# lattepanda_driverstation.net
KiCad netlist of a schematic drawn in EAGLE
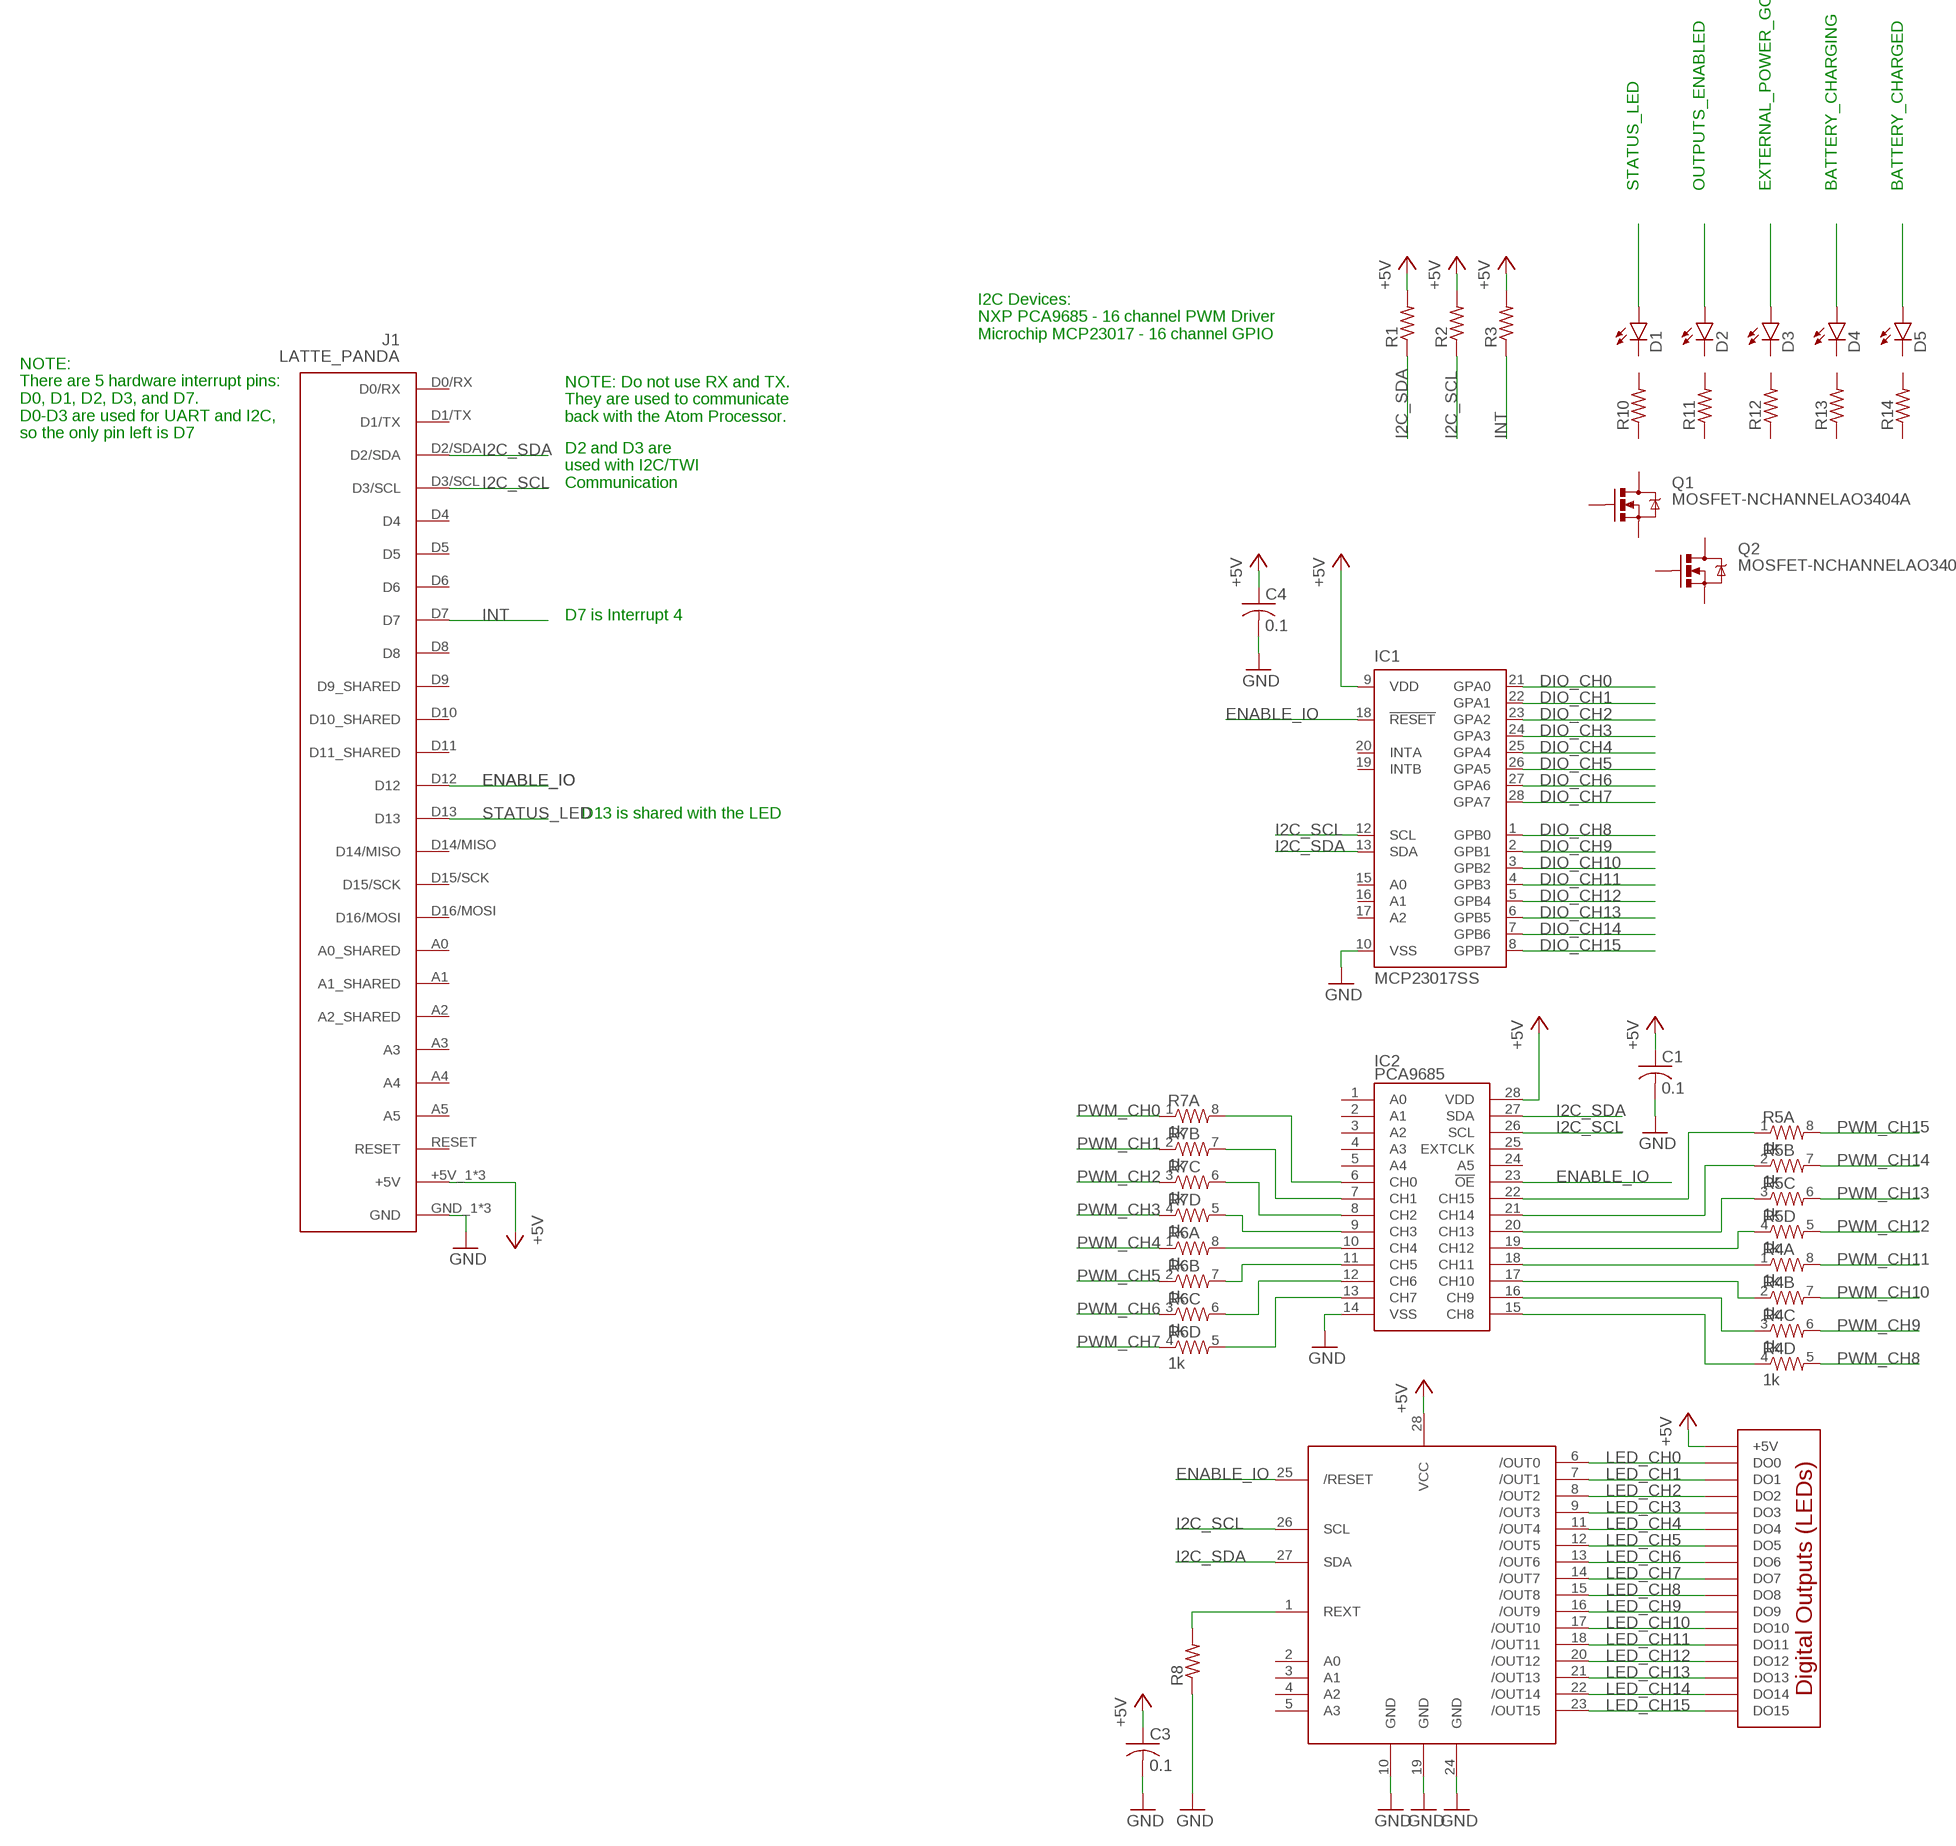
[diagram p0: schematic, sheet 1, part 1 of 2]
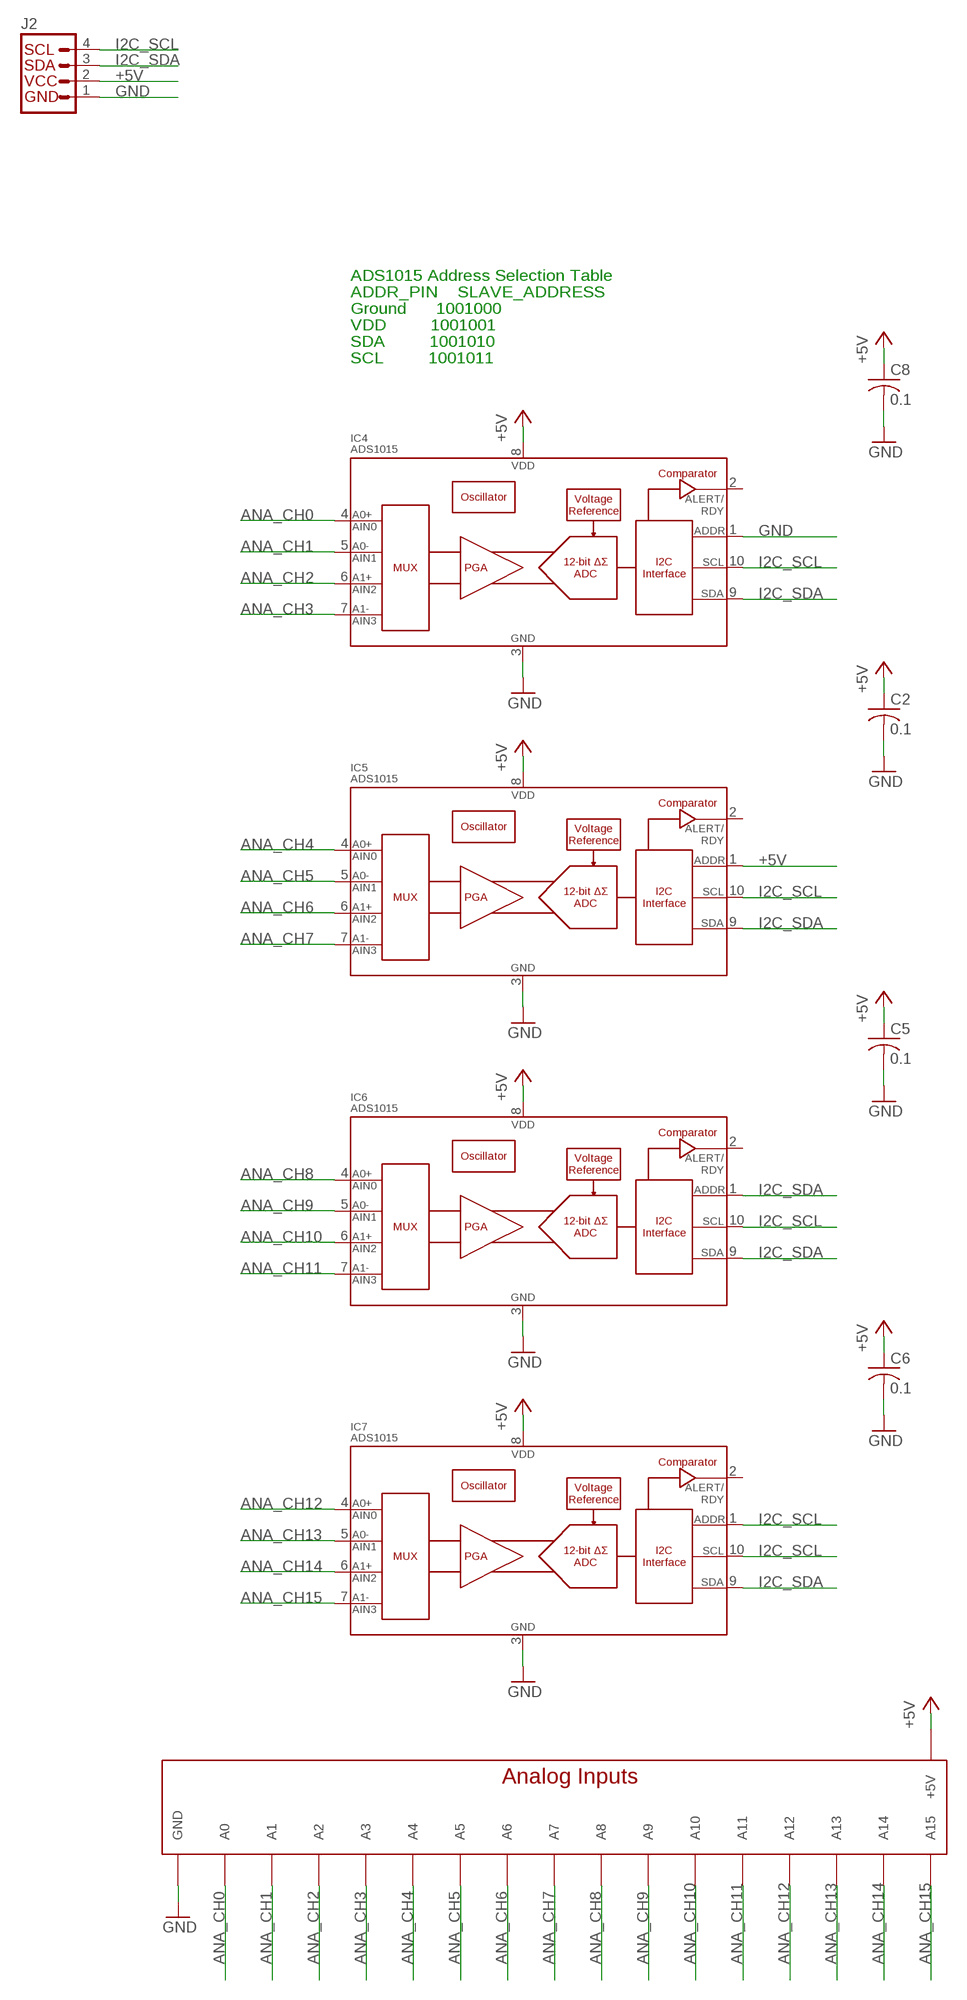
[diagram p1: schematic, sheet 1, part 2 of 2]

(export (version "E")
  (design (tool "Eeschema 10.0.6"))
  (components
    (comp (ref "C1")
      (value "0.1")
      (footprint "eagle-import:C1206")
      (libsource (lib "eagle-import") (part "C-USC1206"))
    )
    (comp (ref "C2")
      (value "0.1")
      (footprint "eagle-import:C1206")
      (libsource (lib "eagle-import") (part "C-USC1206"))
    )
    (comp (ref "C3")
      (value "0.1")
      (footprint "eagle-import:C1206")
      (libsource (lib "eagle-import") (part "C-USC1206"))
    )
    (comp (ref "C4")
      (value "0.1")
      (footprint "eagle-import:C1206")
      (libsource (lib "eagle-import") (part "C-USC1206"))
    )
    (comp (ref "C5")
      (value "0.1")
      (footprint "eagle-import:C1206")
      (libsource (lib "eagle-import") (part "C-USC1206"))
    )
    (comp (ref "C6")
      (value "0.1")
      (footprint "eagle-import:C1206")
      (libsource (lib "eagle-import") (part "C-USC1206"))
    )
    (comp (ref "C8")
      (value "0.1")
      (footprint "eagle-import:C1206")
      (libsource (lib "eagle-import") (part "C-USC1206"))
    )
    (comp (ref "D1")
      (value "LED1206")
      (footprint "eagle-import:LED-1206")
      (libsource (lib "eagle-import") (part "LED1206"))
    )
    (comp (ref "D2")
      (value "LED1206")
      (footprint "eagle-import:LED-1206")
      (libsource (lib "eagle-import") (part "LED1206"))
    )
    (comp (ref "D3")
      (value "LED1206")
      (footprint "eagle-import:LED-1206")
      (libsource (lib "eagle-import") (part "LED1206"))
    )
    (comp (ref "D4")
      (value "LED1206")
      (footprint "eagle-import:LED-1206")
      (libsource (lib "eagle-import") (part "LED1206"))
    )
    (comp (ref "D5")
      (value "LED1206")
      (footprint "eagle-import:LED-1206")
      (libsource (lib "eagle-import") (part "LED1206"))
    )
    (comp (ref "IC1")
      (value "MCP23017SS")
      (footprint "eagle-import:SSOP28")
      (fields (field (name "MF") "MICROCHIP") (field (name "MPN") "MCP23017-E/SS"))
      (libsource (lib "eagle-import") (part "MCP23017SS"))
    )
    (comp (ref "IC2")
      (value "PCA9685")
      (footprint "eagle-import:TSSOP-28_4MM")
      (libsource (lib "eagle-import") (part "PCA9685"))
    )
    (comp (ref "IC3")
      (value "TLC59116")
      (footprint "eagle-import:TSSOP28")
      (libsource (lib "eagle-import") (part "TLC59116"))
    )
    (comp (ref "IC4")
      (value "ADS1015")
      (footprint "eagle-import:MSOP10")
      (libsource (lib "eagle-import") (part "ADS1015"))
    )
    (comp (ref "IC5")
      (value "ADS1015")
      (footprint "eagle-import:MSOP10")
      (libsource (lib "eagle-import") (part "ADS1015"))
    )
    (comp (ref "IC6")
      (value "ADS1015")
      (footprint "eagle-import:MSOP10")
      (libsource (lib "eagle-import") (part "ADS1015"))
    )
    (comp (ref "IC7")
      (value "ADS1015")
      (footprint "eagle-import:MSOP10")
      (libsource (lib "eagle-import") (part "ADS1015"))
    )
    (comp (ref "J1")
      (value "LATTE_PANDA")
      (footprint "eagle-import:LATTE_PANDA")
      (libsource (lib "eagle-import") (part "LATTE_PANDA"))
    )
    (comp (ref "J2")
      (value "I2C_STANDARD")
      (footprint "eagle-import:1X04")
      (libsource (lib "eagle-import") (part "I2C_STANDARD"))
    )
    (comp (ref "Q1")
      (value "MOSFET-NCHANNELAO3404A")
      (footprint "eagle-import:SOT23-3")
      (libsource (lib "eagle-import") (part "MOSFET-NCHANNELAO3404A"))
    )
    (comp (ref "Q2")
      (value "MOSFET-NCHANNELAO3404A")
      (footprint "eagle-import:SOT23-3")
      (libsource (lib "eagle-import") (part "MOSFET-NCHANNELAO3404A"))
    )
    (comp (ref "R1")
      (value "R-US_M1206")
      (footprint "eagle-import:M1206")
      (libsource (lib "eagle-import") (part "R-US_M1206"))
    )
    (comp (ref "R2")
      (value "R-US_M1206")
      (footprint "eagle-import:M1206")
      (libsource (lib "eagle-import") (part "R-US_M1206"))
    )
    (comp (ref "R3")
      (value "R-US_M1206")
      (footprint "eagle-import:M1206")
      (libsource (lib "eagle-import") (part "R-US_M1206"))
    )
    (comp (ref "R4")
      (value "1k")
      (footprint "eagle-import:0603-ARV")
      (libsource (lib "eagle-import") (part "RESISTOR-ARRAY0603-ARV"))
    )
    (comp (ref "R5")
      (value "1k")
      (footprint "eagle-import:0603-ARV")
      (libsource (lib "eagle-import") (part "RESISTOR-ARRAY0603-ARV"))
    )
    (comp (ref "R6")
      (value "1k")
      (footprint "eagle-import:0603-ARV")
      (libsource (lib "eagle-import") (part "RESISTOR-ARRAY0603-ARV"))
    )
    (comp (ref "R7")
      (value "1k")
      (footprint "eagle-import:0603-ARV")
      (libsource (lib "eagle-import") (part "RESISTOR-ARRAY0603-ARV"))
    )
    (comp (ref "R8")
      (value "R-US_R1206")
      (footprint "eagle-import:R1206")
      (libsource (lib "eagle-import") (part "R-US_R1206"))
    )
    (comp (ref "R10")
      (value "R-US_M1206")
      (footprint "eagle-import:M1206")
      (libsource (lib "eagle-import") (part "R-US_M1206"))
    )
    (comp (ref "R11")
      (value "R-US_M1206")
      (footprint "eagle-import:M1206")
      (libsource (lib "eagle-import") (part "R-US_M1206"))
    )
    (comp (ref "R12")
      (value "R-US_M1206")
      (footprint "eagle-import:M1206")
      (libsource (lib "eagle-import") (part "R-US_M1206"))
    )
    (comp (ref "R13")
      (value "R-US_M1206")
      (footprint "eagle-import:M1206")
      (libsource (lib "eagle-import") (part "R-US_M1206"))
    )
    (comp (ref "R14")
      (value "R-US_M1206")
      (footprint "eagle-import:M1206")
      (libsource (lib "eagle-import") (part "R-US_M1206"))
    )
    (comp (ref "U$1")
      (value "ANALOGHEADER")
      (footprint "eagle-import:ANALOGHEADER")
      (libsource (lib "eagle-import") (part "ANALOGHEADER"))
    )
    (comp (ref "U$2")
      (value "DIGITALOUTPUTS")
      (footprint "eagle-import:DIGITALOUT")
      (libsource (lib "eagle-import") (part "DIGITALOUTPUTS"))
    )
  )
  (nets
    (net (code "1") (name "+5V") (class "Default")
      (node (ref "C1") (pin "1") (pinfunction "1_1") (pintype "passive"))
      (node (ref "C2") (pin "1") (pinfunction "1_1") (pintype "passive"))
      (node (ref "C3") (pin "1") (pinfunction "1_1") (pintype "passive"))
      (node (ref "C4") (pin "1") (pinfunction "1_1") (pintype "passive"))
      (node (ref "C5") (pin "1") (pinfunction "1_1") (pintype "passive"))
      (node (ref "C6") (pin "1") (pinfunction "1_1") (pintype "passive"))
      (node (ref "C8") (pin "1") (pinfunction "1_1") (pintype "passive"))
      (node (ref "IC1") (pin "9") (pinfunction "VDD_9") (pintype "power_in"))
      (node (ref "IC2") (pin "28") (pinfunction "VDD_28") (pintype "bidirectional"))
      (node (ref "IC3") (pin "28") (pinfunction "VCC_28") (pintype "bidirectional"))
      (node (ref "IC4") (pin "8") (pinfunction "VDD_8") (pintype "bidirectional"))
      (node (ref "IC5") (pin "1") (pinfunction "ADDR_1") (pintype "bidirectional"))
      (node (ref "IC5") (pin "8") (pinfunction "VDD_8") (pintype "bidirectional"))
      (node (ref "IC6") (pin "8") (pinfunction "VDD_8") (pintype "bidirectional"))
      (node (ref "IC7") (pin "8") (pinfunction "VDD_8") (pintype "bidirectional"))
      (node (ref "J1") (pin "+5V_1") (pinfunction "+5V_+5V_1") (pintype "power_in"))
      (node (ref "J1") (pin "+5V_2") (pinfunction "+5V_+5V_2") (pintype "power_in"))
      (node (ref "J1") (pin "+5V_3") (pinfunction "+5V_+5V_3") (pintype "power_in"))
      (node (ref "J2") (pin "2") (pinfunction "2_2") (pintype "passive"))
      (node (ref "R1") (pin "2") (pinfunction "2_2") (pintype "passive"))
      (node (ref "R2") (pin "2") (pinfunction "2_2") (pintype "passive"))
      (node (ref "R3") (pin "2") (pinfunction "2_2") (pintype "passive"))
      (node (ref "U$1") (pin "+5V@0") (pinfunction "+5V_+5V@0") (pintype "bidirectional"))
      (node (ref "U$1") (pin "+5V@1") (pinfunction "+5V_+5V@1") (pintype "bidirectional"))
      (node (ref "U$1") (pin "+5V@10") (pinfunction "+5V_+5V@10") (pintype "bidirectional"))
      (node (ref "U$1") (pin "+5V@11") (pinfunction "+5V_+5V@11") (pintype "bidirectional"))
      (node (ref "U$1") (pin "+5V@12") (pinfunction "+5V_+5V@12") (pintype "bidirectional"))
      (node (ref "U$1") (pin "+5V@13") (pinfunction "+5V_+5V@13") (pintype "bidirectional"))
      (node (ref "U$1") (pin "+5V@14") (pinfunction "+5V_+5V@14") (pintype "bidirectional"))
      (node (ref "U$1") (pin "+5V@15") (pinfunction "+5V_+5V@15") (pintype "bidirectional"))
      (node (ref "U$1") (pin "+5V@2") (pinfunction "+5V_+5V@2") (pintype "bidirectional"))
      (node (ref "U$1") (pin "+5V@3") (pinfunction "+5V_+5V@3") (pintype "bidirectional"))
      (node (ref "U$1") (pin "+5V@4") (pinfunction "+5V_+5V@4") (pintype "bidirectional"))
      (node (ref "U$1") (pin "+5V@5") (pinfunction "+5V_+5V@5") (pintype "bidirectional"))
      (node (ref "U$1") (pin "+5V@6") (pinfunction "+5V_+5V@6") (pintype "bidirectional"))
      (node (ref "U$1") (pin "+5V@7") (pinfunction "+5V_+5V@7") (pintype "bidirectional"))
      (node (ref "U$1") (pin "+5V@8") (pinfunction "+5V_+5V@8") (pintype "bidirectional"))
      (node (ref "U$1") (pin "+5V@9") (pinfunction "+5V_+5V@9") (pintype "bidirectional"))
      (node (ref "U$2") (pin "+5V@0") (pinfunction "+5V_+5V@0") (pintype "power_in"))
      (node (ref "U$2") (pin "+5V@1") (pinfunction "+5V_+5V@1") (pintype "power_in"))
      (node (ref "U$2") (pin "+5V@10") (pinfunction "+5V_+5V@10") (pintype "power_in"))
      (node (ref "U$2") (pin "+5V@11") (pinfunction "+5V_+5V@11") (pintype "power_in"))
      (node (ref "U$2") (pin "+5V@12") (pinfunction "+5V_+5V@12") (pintype "power_in"))
      (node (ref "U$2") (pin "+5V@13") (pinfunction "+5V_+5V@13") (pintype "power_in"))
      (node (ref "U$2") (pin "+5V@14") (pinfunction "+5V_+5V@14") (pintype "power_in"))
      (node (ref "U$2") (pin "+5V@15") (pinfunction "+5V_+5V@15") (pintype "power_in"))
      (node (ref "U$2") (pin "+5V@2") (pinfunction "+5V_+5V@2") (pintype "power_in"))
      (node (ref "U$2") (pin "+5V@3") (pinfunction "+5V_+5V@3") (pintype "power_in"))
      (node (ref "U$2") (pin "+5V@4") (pinfunction "+5V_+5V@4") (pintype "power_in"))
      (node (ref "U$2") (pin "+5V@5") (pinfunction "+5V_+5V@5") (pintype "power_in"))
      (node (ref "U$2") (pin "+5V@6") (pinfunction "+5V_+5V@6") (pintype "power_in"))
      (node (ref "U$2") (pin "+5V@7") (pinfunction "+5V_+5V@7") (pintype "power_in"))
      (node (ref "U$2") (pin "+5V@8") (pinfunction "+5V_+5V@8") (pintype "power_in"))
      (node (ref "U$2") (pin "+5V@9") (pinfunction "+5V_+5V@9") (pintype "power_in"))
    )
    (net (code "2") (name "/ANA_CH0") (class "Default")
      (node (ref "IC4") (pin "4") (pinfunction "AIN0_4") (pintype "bidirectional"))
      (node (ref "U$1") (pin "0") (pinfunction "A0_0") (pintype "bidirectional"))
    )
    (net (code "3") (name "/ANA_CH1") (class "Default")
      (node (ref "IC4") (pin "5") (pinfunction "AIN1_5") (pintype "bidirectional"))
      (node (ref "U$1") (pin "1") (pinfunction "A1_1") (pintype "bidirectional"))
    )
    (net (code "4") (name "/ANA_CH2") (class "Default")
      (node (ref "IC4") (pin "6") (pinfunction "AIN2_6") (pintype "bidirectional"))
      (node (ref "U$1") (pin "2") (pinfunction "A2_2") (pintype "bidirectional"))
    )
    (net (code "5") (name "/ANA_CH3") (class "Default")
      (node (ref "IC4") (pin "7") (pinfunction "AIN3_7") (pintype "bidirectional"))
      (node (ref "U$1") (pin "3") (pinfunction "A3_3") (pintype "bidirectional"))
    )
    (net (code "6") (name "/ANA_CH4") (class "Default")
      (node (ref "IC5") (pin "4") (pinfunction "AIN0_4") (pintype "bidirectional"))
      (node (ref "U$1") (pin "4") (pinfunction "A4_4") (pintype "bidirectional"))
    )
    (net (code "7") (name "/ANA_CH5") (class "Default")
      (node (ref "IC5") (pin "5") (pinfunction "AIN1_5") (pintype "bidirectional"))
      (node (ref "U$1") (pin "5") (pinfunction "A5_5") (pintype "bidirectional"))
    )
    (net (code "8") (name "/ANA_CH6") (class "Default")
      (node (ref "IC5") (pin "6") (pinfunction "AIN2_6") (pintype "bidirectional"))
      (node (ref "U$1") (pin "6") (pinfunction "A6_6") (pintype "bidirectional"))
    )
    (net (code "9") (name "/ANA_CH7") (class "Default")
      (node (ref "IC5") (pin "7") (pinfunction "AIN3_7") (pintype "bidirectional"))
      (node (ref "U$1") (pin "7") (pinfunction "A7_7") (pintype "bidirectional"))
    )
    (net (code "10") (name "/ANA_CH8") (class "Default")
      (node (ref "IC6") (pin "4") (pinfunction "AIN0_4") (pintype "bidirectional"))
      (node (ref "U$1") (pin "8") (pinfunction "A8_8") (pintype "bidirectional"))
    )
    (net (code "11") (name "/ANA_CH9") (class "Default")
      (node (ref "IC6") (pin "5") (pinfunction "AIN1_5") (pintype "bidirectional"))
      (node (ref "U$1") (pin "9") (pinfunction "A9_9") (pintype "bidirectional"))
    )
    (net (code "12") (name "/ANA_CH10") (class "Default")
      (node (ref "IC6") (pin "6") (pinfunction "AIN2_6") (pintype "bidirectional"))
      (node (ref "U$1") (pin "10") (pinfunction "A10_10") (pintype "bidirectional"))
    )
    (net (code "13") (name "/ANA_CH11") (class "Default")
      (node (ref "IC6") (pin "7") (pinfunction "AIN3_7") (pintype "bidirectional"))
      (node (ref "U$1") (pin "11") (pinfunction "A11_11") (pintype "bidirectional"))
    )
    (net (code "14") (name "/ANA_CH12") (class "Default")
      (node (ref "IC7") (pin "4") (pinfunction "AIN0_4") (pintype "bidirectional"))
      (node (ref "U$1") (pin "12") (pinfunction "A12_12") (pintype "bidirectional"))
    )
    (net (code "15") (name "/ANA_CH13") (class "Default")
      (node (ref "IC7") (pin "5") (pinfunction "AIN1_5") (pintype "bidirectional"))
      (node (ref "U$1") (pin "13") (pinfunction "A13_13") (pintype "bidirectional"))
    )
    (net (code "16") (name "/ANA_CH14") (class "Default")
      (node (ref "IC7") (pin "6") (pinfunction "AIN2_6") (pintype "bidirectional"))
      (node (ref "U$1") (pin "14") (pinfunction "A14_14") (pintype "bidirectional"))
    )
    (net (code "17") (name "/ANA_CH15") (class "Default")
      (node (ref "IC7") (pin "7") (pinfunction "AIN3_7") (pintype "bidirectional"))
      (node (ref "U$1") (pin "15") (pinfunction "A15_15") (pintype "bidirectional"))
    )
    (net (code "18") (name "/DIO_CH0") (class "Default")
      (node (ref "IC1") (pin "21") (pinfunction "GPA0_21") (pintype "bidirectional"))
    )
    (net (code "19") (name "/DIO_CH1") (class "Default")
      (node (ref "IC1") (pin "22") (pinfunction "GPA1_22") (pintype "bidirectional"))
    )
    (net (code "20") (name "/DIO_CH2") (class "Default")
      (node (ref "IC1") (pin "23") (pinfunction "GPA2_23") (pintype "bidirectional"))
    )
    (net (code "21") (name "/DIO_CH3") (class "Default")
      (node (ref "IC1") (pin "24") (pinfunction "GPA3_24") (pintype "bidirectional"))
    )
    (net (code "22") (name "/DIO_CH4") (class "Default")
      (node (ref "IC1") (pin "25") (pinfunction "GPA4_25") (pintype "bidirectional"))
    )
    (net (code "23") (name "/DIO_CH5") (class "Default")
      (node (ref "IC1") (pin "26") (pinfunction "GPA5_26") (pintype "bidirectional"))
    )
    (net (code "24") (name "/DIO_CH6") (class "Default")
      (node (ref "IC1") (pin "27") (pinfunction "GPA6_27") (pintype "bidirectional"))
    )
    (net (code "25") (name "/DIO_CH7") (class "Default")
      (node (ref "IC1") (pin "28") (pinfunction "GPA7_28") (pintype "bidirectional"))
    )
    (net (code "26") (name "/DIO_CH8") (class "Default")
      (node (ref "IC1") (pin "1") (pinfunction "GPB0_1") (pintype "bidirectional"))
    )
    (net (code "27") (name "/DIO_CH9") (class "Default")
      (node (ref "IC1") (pin "2") (pinfunction "GPB1_2") (pintype "bidirectional"))
    )
    (net (code "28") (name "/DIO_CH10") (class "Default")
      (node (ref "IC1") (pin "3") (pinfunction "GPB2_3") (pintype "bidirectional"))
    )
    (net (code "29") (name "/DIO_CH11") (class "Default")
      (node (ref "IC1") (pin "4") (pinfunction "GPB3_4") (pintype "bidirectional"))
    )
    (net (code "30") (name "/DIO_CH12") (class "Default")
      (node (ref "IC1") (pin "5") (pinfunction "GPB4_5") (pintype "bidirectional"))
    )
    (net (code "31") (name "/DIO_CH13") (class "Default")
      (node (ref "IC1") (pin "6") (pinfunction "GPB5_6") (pintype "bidirectional"))
    )
    (net (code "32") (name "/DIO_CH14") (class "Default")
      (node (ref "IC1") (pin "7") (pinfunction "GPB6_7") (pintype "bidirectional"))
    )
    (net (code "33") (name "/DIO_CH15") (class "Default")
      (node (ref "IC1") (pin "8") (pinfunction "GPB7_8") (pintype "bidirectional"))
    )
    (net (code "34") (name "/ENABLE_IO") (class "Default")
      (node (ref "IC1") (pin "18") (pinfunction "~{RESET}_18") (pintype "input"))
      (node (ref "IC2") (pin "23") (pinfunction "~{OE}_23") (pintype "bidirectional"))
      (node (ref "IC3") (pin "25") (pinfunction "/RESET_25") (pintype "bidirectional"))
      (node (ref "J1") (pin "D12") (pinfunction "D12_D12") (pintype "bidirectional"))
    )
    (net (code "35") (name "/I2C_SCL") (class "Default")
      (node (ref "IC1") (pin "12") (pinfunction "SCL_12") (pintype "input"))
      (node (ref "IC2") (pin "26") (pinfunction "SCL_26") (pintype "bidirectional"))
      (node (ref "IC3") (pin "26") (pinfunction "SCL_26") (pintype "bidirectional"))
      (node (ref "IC4") (pin "10") (pinfunction "SCL_10") (pintype "bidirectional"))
      (node (ref "IC5") (pin "10") (pinfunction "SCL_10") (pintype "bidirectional"))
      (node (ref "IC6") (pin "10") (pinfunction "SCL_10") (pintype "bidirectional"))
      (node (ref "IC7") (pin "1") (pinfunction "ADDR_1") (pintype "bidirectional"))
      (node (ref "IC7") (pin "10") (pinfunction "SCL_10") (pintype "bidirectional"))
      (node (ref "J1") (pin "D3/SCL") (pinfunction "D3/SCL_D3/SCL") (pintype "bidirectional"))
      (node (ref "J2") (pin "4") (pinfunction "4_4") (pintype "passive"))
      (node (ref "R2") (pin "1") (pinfunction "1_1") (pintype "passive"))
    )
    (net (code "36") (name "/I2C_SDA") (class "Default")
      (node (ref "IC1") (pin "13") (pinfunction "SDA_13") (pintype "bidirectional"))
      (node (ref "IC2") (pin "27") (pinfunction "SDA_27") (pintype "bidirectional"))
      (node (ref "IC3") (pin "27") (pinfunction "SDA_27") (pintype "bidirectional"))
      (node (ref "IC4") (pin "9") (pinfunction "SDA_9") (pintype "bidirectional"))
      (node (ref "IC5") (pin "9") (pinfunction "SDA_9") (pintype "bidirectional"))
      (node (ref "IC6") (pin "1") (pinfunction "ADDR_1") (pintype "bidirectional"))
      (node (ref "IC6") (pin "9") (pinfunction "SDA_9") (pintype "bidirectional"))
      (node (ref "IC7") (pin "9") (pinfunction "SDA_9") (pintype "bidirectional"))
      (node (ref "J1") (pin "D2/SDA") (pinfunction "D2/SDA_D2/SDA") (pintype "bidirectional"))
      (node (ref "J2") (pin "3") (pinfunction "3_3") (pintype "passive"))
      (node (ref "R1") (pin "1") (pinfunction "1_1") (pintype "passive"))
    )
    (net (code "37") (name "/INT") (class "Default")
      (node (ref "J1") (pin "D7") (pinfunction "D7_D7") (pintype "bidirectional"))
      (node (ref "R3") (pin "1") (pinfunction "1_1") (pintype "passive"))
    )
    (net (code "38") (name "/LED_CH0") (class "Default")
      (node (ref "IC3") (pin "6") (pinfunction "/OUT0_6") (pintype "bidirectional"))
      (node (ref "U$2") (pin "DO0") (pinfunction "DO0_DO0") (pintype "bidirectional"))
    )
    (net (code "39") (name "/LED_CH1") (class "Default")
      (node (ref "IC3") (pin "7") (pinfunction "/OUT1_7") (pintype "bidirectional"))
      (node (ref "U$2") (pin "DO1") (pinfunction "DO1_DO1") (pintype "bidirectional"))
    )
    (net (code "40") (name "/LED_CH2") (class "Default")
      (node (ref "IC3") (pin "8") (pinfunction "/OUT2_8") (pintype "bidirectional"))
      (node (ref "U$2") (pin "DO2") (pinfunction "DO2_DO2") (pintype "bidirectional"))
    )
    (net (code "41") (name "/LED_CH3") (class "Default")
      (node (ref "IC3") (pin "9") (pinfunction "/OUT3_9") (pintype "bidirectional"))
      (node (ref "U$2") (pin "DO3") (pinfunction "DO3_DO3") (pintype "bidirectional"))
    )
    (net (code "42") (name "/LED_CH4") (class "Default")
      (node (ref "IC3") (pin "11") (pinfunction "/OUT4_11") (pintype "bidirectional"))
      (node (ref "U$2") (pin "DO4") (pinfunction "DO4_DO4") (pintype "bidirectional"))
    )
    (net (code "43") (name "/LED_CH5") (class "Default")
      (node (ref "IC3") (pin "12") (pinfunction "/OUT5_12") (pintype "bidirectional"))
      (node (ref "U$2") (pin "DO5") (pinfunction "DO5_DO5") (pintype "bidirectional"))
    )
    (net (code "44") (name "/LED_CH6") (class "Default")
      (node (ref "IC3") (pin "13") (pinfunction "/OUT6_13") (pintype "bidirectional"))
      (node (ref "U$2") (pin "DO6") (pinfunction "DO6_DO6") (pintype "bidirectional"))
    )
    (net (code "45") (name "/LED_CH7") (class "Default")
      (node (ref "IC3") (pin "14") (pinfunction "/OUT7_14") (pintype "bidirectional"))
      (node (ref "U$2") (pin "DO7") (pinfunction "DO7_DO7") (pintype "bidirectional"))
    )
    (net (code "46") (name "/LED_CH8") (class "Default")
      (node (ref "IC3") (pin "15") (pinfunction "/OUT8_15") (pintype "bidirectional"))
      (node (ref "U$2") (pin "DO8") (pinfunction "DO8_DO8") (pintype "bidirectional"))
    )
    (net (code "47") (name "/LED_CH9") (class "Default")
      (node (ref "IC3") (pin "16") (pinfunction "/OUT9_16") (pintype "bidirectional"))
      (node (ref "U$2") (pin "DO9") (pinfunction "DO9_DO9") (pintype "bidirectional"))
    )
    (net (code "48") (name "/LED_CH10") (class "Default")
      (node (ref "IC3") (pin "17") (pinfunction "/OUT10_17") (pintype "bidirectional"))
      (node (ref "U$2") (pin "DO10") (pinfunction "DO10_DO10") (pintype "bidirectional"))
    )
    (net (code "49") (name "/LED_CH11") (class "Default")
      (node (ref "IC3") (pin "18") (pinfunction "/OUT11_18") (pintype "bidirectional"))
      (node (ref "U$2") (pin "DO11") (pinfunction "DO11_DO11") (pintype "bidirectional"))
    )
    (net (code "50") (name "/LED_CH12") (class "Default")
      (node (ref "IC3") (pin "20") (pinfunction "/OUT12_20") (pintype "bidirectional"))
      (node (ref "U$2") (pin "DO12") (pinfunction "DO12_DO12") (pintype "bidirectional"))
    )
    (net (code "51") (name "/LED_CH13") (class "Default")
      (node (ref "IC3") (pin "21") (pinfunction "/OUT13_21") (pintype "bidirectional"))
      (node (ref "U$2") (pin "DO13") (pinfunction "DO13_DO13") (pintype "bidirectional"))
    )
    (net (code "52") (name "/LED_CH14") (class "Default")
      (node (ref "IC3") (pin "22") (pinfunction "/OUT14_22") (pintype "bidirectional"))
      (node (ref "U$2") (pin "DO14") (pinfunction "DO14_DO14") (pintype "bidirectional"))
    )
    (net (code "53") (name "/LED_CH15") (class "Default")
      (node (ref "IC3") (pin "23") (pinfunction "/OUT15_23") (pintype "bidirectional"))
      (node (ref "U$2") (pin "DO15") (pinfunction "DO15_DO15") (pintype "bidirectional"))
    )
    (net (code "54") (name "/PWM_CH0") (class "Default")
      (node (ref "R7") (pin "1") (pinfunction "1_1") (pintype "passive"))
    )
    (net (code "55") (name "/PWM_CH1") (class "Default")
      (node (ref "R7") (pin "2") (pinfunction "1_2") (pintype "passive"))
    )
    (net (code "56") (name "/PWM_CH2") (class "Default")
      (node (ref "R7") (pin "3") (pinfunction "1_3") (pintype "passive"))
    )
    (net (code "57") (name "/PWM_CH3") (class "Default")
      (node (ref "R7") (pin "4") (pinfunction "1_4") (pintype "passive"))
    )
    (net (code "58") (name "/PWM_CH4") (class "Default")
      (node (ref "R6") (pin "1") (pinfunction "1_1") (pintype "passive"))
    )
    (net (code "59") (name "/PWM_CH5") (class "Default")
      (node (ref "R6") (pin "2") (pinfunction "1_2") (pintype "passive"))
    )
    (net (code "60") (name "/PWM_CH6") (class "Default")
      (node (ref "R6") (pin "3") (pinfunction "1_3") (pintype "passive"))
    )
    (net (code "61") (name "/PWM_CH7") (class "Default")
      (node (ref "R6") (pin "4") (pinfunction "1_4") (pintype "passive"))
    )
    (net (code "62") (name "/PWM_CH8") (class "Default")
      (node (ref "R4") (pin "5") (pinfunction "2_5") (pintype "passive"))
    )
    (net (code "63") (name "/PWM_CH9") (class "Default")
      (node (ref "R4") (pin "6") (pinfunction "2_6") (pintype "passive"))
    )
    (net (code "64") (name "/PWM_CH10") (class "Default")
      (node (ref "R4") (pin "7") (pinfunction "2_7") (pintype "passive"))
    )
    (net (code "65") (name "/PWM_CH11") (class "Default")
      (node (ref "R4") (pin "8") (pinfunction "2_8") (pintype "passive"))
    )
    (net (code "66") (name "/PWM_CH12") (class "Default")
      (node (ref "R5") (pin "5") (pinfunction "2_5") (pintype "passive"))
    )
    (net (code "67") (name "/PWM_CH13") (class "Default")
      (node (ref "R5") (pin "6") (pinfunction "2_6") (pintype "passive"))
    )
    (net (code "68") (name "/PWM_CH14") (class "Default")
      (node (ref "R5") (pin "7") (pinfunction "2_7") (pintype "passive"))
    )
    (net (code "69") (name "/PWM_CH15") (class "Default")
      (node (ref "R5") (pin "8") (pinfunction "2_8") (pintype "passive"))
    )
    (net (code "70") (name "/STATUS_LED") (class "Default")
      (node (ref "J1") (pin "D13") (pinfunction "D13_D13") (pintype "bidirectional"))
    )
    (net (code "71") (name "GND") (class "Default")
      (node (ref "C1") (pin "2") (pinfunction "2_2") (pintype "passive"))
      (node (ref "C2") (pin "2") (pinfunction "2_2") (pintype "passive"))
      (node (ref "C3") (pin "2") (pinfunction "2_2") (pintype "passive"))
      (node (ref "C4") (pin "2") (pinfunction "2_2") (pintype "passive"))
      (node (ref "C5") (pin "2") (pinfunction "2_2") (pintype "passive"))
      (node (ref "C6") (pin "2") (pinfunction "2_2") (pintype "passive"))
      (node (ref "C8") (pin "2") (pinfunction "2_2") (pintype "passive"))
      (node (ref "IC1") (pin "10") (pinfunction "VSS_10") (pintype "power_in"))
      (node (ref "IC2") (pin "14") (pinfunction "VSS_14") (pintype "bidirectional"))
      (node (ref "IC3") (pin "10") (pinfunction "GND_10") (pintype "bidirectional"))
      (node (ref "IC3") (pin "19") (pinfunction "GND_19") (pintype "bidirectional"))
      (node (ref "IC3") (pin "24") (pinfunction "GND_24") (pintype "bidirectional"))
      (node (ref "IC4") (pin "1") (pinfunction "ADDR_1") (pintype "bidirectional"))
      (node (ref "IC4") (pin "3") (pinfunction "VSS_3") (pintype "bidirectional"))
      (node (ref "IC5") (pin "3") (pinfunction "VSS_3") (pintype "bidirectional"))
      (node (ref "IC6") (pin "3") (pinfunction "VSS_3") (pintype "bidirectional"))
      (node (ref "IC7") (pin "3") (pinfunction "VSS_3") (pintype "bidirectional"))
      (node (ref "J1") (pin "GND_1") (pinfunction "GND_GND_1") (pintype "power_in"))
      (node (ref "J1") (pin "GND_2") (pinfunction "GND_GND_2") (pintype "power_in"))
      (node (ref "J1") (pin "GND_3") (pinfunction "GND_GND_3") (pintype "power_in"))
      (node (ref "J2") (pin "1") (pinfunction "1_1") (pintype "passive"))
      (node (ref "R8") (pin "1") (pinfunction "1_1") (pintype "passive"))
      (node (ref "U$1") (pin "GND@0") (pinfunction "GND_GND@0") (pintype "bidirectional"))
      (node (ref "U$1") (pin "GND@1") (pinfunction "GND_GND@1") (pintype "bidirectional"))
      (node (ref "U$1") (pin "GND@10") (pinfunction "GND_GND@10") (pintype "bidirectional"))
      (node (ref "U$1") (pin "GND@11") (pinfunction "GND_GND@11") (pintype "bidirectional"))
      (node (ref "U$1") (pin "GND@12") (pinfunction "GND_GND@12") (pintype "bidirectional"))
      (node (ref "U$1") (pin "GND@13") (pinfunction "GND_GND@13") (pintype "bidirectional"))
      (node (ref "U$1") (pin "GND@14") (pinfunction "GND_GND@14") (pintype "bidirectional"))
      (node (ref "U$1") (pin "GND@15") (pinfunction "GND_GND@15") (pintype "bidirectional"))
      (node (ref "U$1") (pin "GND@2") (pinfunction "GND_GND@2") (pintype "bidirectional"))
      (node (ref "U$1") (pin "GND@3") (pinfunction "GND_GND@3") (pintype "bidirectional"))
      (node (ref "U$1") (pin "GND@4") (pinfunction "GND_GND@4") (pintype "bidirectional"))
      (node (ref "U$1") (pin "GND@5") (pinfunction "GND_GND@5") (pintype "bidirectional"))
      (node (ref "U$1") (pin "GND@6") (pinfunction "GND_GND@6") (pintype "bidirectional"))
      (node (ref "U$1") (pin "GND@7") (pinfunction "GND_GND@7") (pintype "bidirectional"))
      (node (ref "U$1") (pin "GND@8") (pinfunction "GND_GND@8") (pintype "bidirectional"))
      (node (ref "U$1") (pin "GND@9") (pinfunction "GND_GND@9") (pintype "bidirectional"))
    )
    (net (code "72") (name "Net-(IC2-CH0)") (class "Default")
      (node (ref "IC2") (pin "6") (pinfunction "CH0_6") (pintype "bidirectional"))
      (node (ref "R7") (pin "8") (pinfunction "2_8") (pintype "passive"))
    )
    (net (code "73") (name "Net-(IC2-CH1)") (class "Default")
      (node (ref "IC2") (pin "7") (pinfunction "CH1_7") (pintype "bidirectional"))
      (node (ref "R7") (pin "7") (pinfunction "2_7") (pintype "passive"))
    )
    (net (code "74") (name "Net-(IC2-CH2)") (class "Default")
      (node (ref "IC2") (pin "8") (pinfunction "CH2_8") (pintype "bidirectional"))
      (node (ref "R7") (pin "6") (pinfunction "2_6") (pintype "passive"))
    )
    (net (code "75") (name "Net-(IC2-CH3)") (class "Default")
      (node (ref "IC2") (pin "9") (pinfunction "CH3_9") (pintype "bidirectional"))
      (node (ref "R7") (pin "5") (pinfunction "2_5") (pintype "passive"))
    )
    (net (code "76") (name "Net-(IC2-CH4)") (class "Default")
      (node (ref "IC2") (pin "10") (pinfunction "CH4_10") (pintype "bidirectional"))
      (node (ref "R6") (pin "8") (pinfunction "2_8") (pintype "passive"))
    )
    (net (code "77") (name "Net-(IC2-CH5)") (class "Default")
      (node (ref "IC2") (pin "11") (pinfunction "CH5_11") (pintype "bidirectional"))
      (node (ref "R6") (pin "7") (pinfunction "2_7") (pintype "passive"))
    )
    (net (code "78") (name "Net-(IC2-CH6)") (class "Default")
      (node (ref "IC2") (pin "12") (pinfunction "CH6_12") (pintype "bidirectional"))
      (node (ref "R6") (pin "6") (pinfunction "2_6") (pintype "passive"))
    )
    (net (code "79") (name "Net-(IC2-CH7)") (class "Default")
      (node (ref "IC2") (pin "13") (pinfunction "CH7_13") (pintype "bidirectional"))
      (node (ref "R6") (pin "5") (pinfunction "2_5") (pintype "passive"))
    )
    (net (code "80") (name "Net-(IC2-CH8)") (class "Default")
      (node (ref "IC2") (pin "15") (pinfunction "CH8_15") (pintype "bidirectional"))
      (node (ref "R4") (pin "4") (pinfunction "1_4") (pintype "passive"))
    )
    (net (code "81") (name "Net-(IC2-CH9)") (class "Default")
      (node (ref "IC2") (pin "16") (pinfunction "CH9_16") (pintype "bidirectional"))
      (node (ref "R4") (pin "3") (pinfunction "1_3") (pintype "passive"))
    )
    (net (code "82") (name "Net-(IC2-CH10)") (class "Default")
      (node (ref "IC2") (pin "17") (pinfunction "CH10_17") (pintype "bidirectional"))
      (node (ref "R4") (pin "2") (pinfunction "1_2") (pintype "passive"))
    )
    (net (code "83") (name "Net-(IC2-CH11)") (class "Default")
      (node (ref "IC2") (pin "18") (pinfunction "CH11_18") (pintype "bidirectional"))
      (node (ref "R4") (pin "1") (pinfunction "1_1") (pintype "passive"))
    )
    (net (code "84") (name "Net-(IC2-CH12)") (class "Default")
      (node (ref "IC2") (pin "19") (pinfunction "CH12_19") (pintype "bidirectional"))
      (node (ref "R5") (pin "4") (pinfunction "1_4") (pintype "passive"))
    )
    (net (code "85") (name "Net-(IC2-CH13)") (class "Default")
      (node (ref "IC2") (pin "20") (pinfunction "CH13_20") (pintype "bidirectional"))
      (node (ref "R5") (pin "3") (pinfunction "1_3") (pintype "passive"))
    )
    (net (code "86") (name "Net-(IC2-CH14)") (class "Default")
      (node (ref "IC2") (pin "21") (pinfunction "CH14_21") (pintype "bidirectional"))
      (node (ref "R5") (pin "2") (pinfunction "1_2") (pintype "passive"))
    )
    (net (code "87") (name "Net-(IC2-CH15)") (class "Default")
      (node (ref "IC2") (pin "22") (pinfunction "CH15_22") (pintype "bidirectional"))
      (node (ref "R5") (pin "1") (pinfunction "1_1") (pintype "passive"))
    )
    (net (code "88") (name "Net-(IC3-REXT)") (class "Default")
      (node (ref "IC3") (pin "1") (pinfunction "REXT_1") (pintype "bidirectional"))
      (node (ref "R8") (pin "2") (pinfunction "2_2") (pintype "passive"))
    )
    (net (code "89") (name "unconnected-(D1-PadA)") (class "Default")
      (node (ref "D1") (pin "A") (pinfunction "A_A") (pintype "passive"))
    )
    (net (code "90") (name "unconnected-(D1-PadC)") (class "Default")
      (node (ref "D1") (pin "C") (pinfunction "C_C") (pintype "passive"))
    )
    (net (code "91") (name "unconnected-(D2-PadA)") (class "Default")
      (node (ref "D2") (pin "A") (pinfunction "A_A") (pintype "passive"))
    )
    (net (code "92") (name "unconnected-(D2-PadC)") (class "Default")
      (node (ref "D2") (pin "C") (pinfunction "C_C") (pintype "passive"))
    )
    (net (code "93") (name "unconnected-(D3-PadA)") (class "Default")
      (node (ref "D3") (pin "A") (pinfunction "A_A") (pintype "passive"))
    )
    (net (code "94") (name "unconnected-(D3-PadC)") (class "Default")
      (node (ref "D3") (pin "C") (pinfunction "C_C") (pintype "passive"))
    )
    (net (code "95") (name "unconnected-(D4-PadA)") (class "Default")
      (node (ref "D4") (pin "A") (pinfunction "A_A") (pintype "passive"))
    )
    (net (code "96") (name "unconnected-(D4-PadC)") (class "Default")
      (node (ref "D4") (pin "C") (pinfunction "C_C") (pintype "passive"))
    )
    (net (code "97") (name "unconnected-(D5-PadA)") (class "Default")
      (node (ref "D5") (pin "A") (pinfunction "A_A") (pintype "passive"))
    )
    (net (code "98") (name "unconnected-(D5-PadC)") (class "Default")
      (node (ref "D5") (pin "C") (pinfunction "C_C") (pintype "passive"))
    )
    (net (code "99") (name "unconnected-(IC1-A0-Pad15)") (class "Default")
      (node (ref "IC1") (pin "15") (pinfunction "A0_15") (pintype "input"))
    )
    (net (code "100") (name "unconnected-(IC1-A1-Pad16)") (class "Default")
      (node (ref "IC1") (pin "16") (pinfunction "A1_16") (pintype "input"))
    )
    (net (code "101") (name "unconnected-(IC1-A2-Pad17)") (class "Default")
      (node (ref "IC1") (pin "17") (pinfunction "A2_17") (pintype "input"))
    )
    (net (code "102") (name "unconnected-(IC1-INTA-Pad20)") (class "Default")
      (node (ref "IC1") (pin "20") (pinfunction "INTA_20") (pintype "output"))
    )
    (net (code "103") (name "unconnected-(IC1-INTB-Pad19)") (class "Default")
      (node (ref "IC1") (pin "19") (pinfunction "INTB_19") (pintype "output"))
    )
    (net (code "104") (name "unconnected-(IC2-A0-Pad1)") (class "Default")
      (node (ref "IC2") (pin "1") (pinfunction "A0_1") (pintype "bidirectional"))
    )
    (net (code "105") (name "unconnected-(IC2-A1-Pad2)") (class "Default")
      (node (ref "IC2") (pin "2") (pinfunction "A1_2") (pintype "bidirectional"))
    )
    (net (code "106") (name "unconnected-(IC2-A2-Pad3)") (class "Default")
      (node (ref "IC2") (pin "3") (pinfunction "A2_3") (pintype "bidirectional"))
    )
    (net (code "107") (name "unconnected-(IC2-A3-Pad4)") (class "Default")
      (node (ref "IC2") (pin "4") (pinfunction "A3_4") (pintype "bidirectional"))
    )
    (net (code "108") (name "unconnected-(IC2-A4-Pad5)") (class "Default")
      (node (ref "IC2") (pin "5") (pinfunction "A4_5") (pintype "bidirectional"))
    )
    (net (code "109") (name "unconnected-(IC2-A5-Pad24)") (class "Default")
      (node (ref "IC2") (pin "24") (pinfunction "A5_24") (pintype "bidirectional"))
    )
    (net (code "110") (name "unconnected-(IC2-EXTCLK-Pad25)") (class "Default")
      (node (ref "IC2") (pin "25") (pinfunction "EXTCLK_25") (pintype "bidirectional"))
    )
    (net (code "111") (name "unconnected-(IC3-A0-Pad2)") (class "Default")
      (node (ref "IC3") (pin "2") (pinfunction "A0_2") (pintype "bidirectional"))
    )
    (net (code "112") (name "unconnected-(IC3-A1-Pad3)") (class "Default")
      (node (ref "IC3") (pin "3") (pinfunction "A1_3") (pintype "bidirectional"))
    )
    (net (code "113") (name "unconnected-(IC3-A2-Pad4)") (class "Default")
      (node (ref "IC3") (pin "4") (pinfunction "A2_4") (pintype "bidirectional"))
    )
    (net (code "114") (name "unconnected-(IC3-A3-Pad5)") (class "Default")
      (node (ref "IC3") (pin "5") (pinfunction "A3_5") (pintype "bidirectional"))
    )
    (net (code "115") (name "unconnected-(IC4-ALERT{slash}RDY-Pad2)") (class "Default")
      (node (ref "IC4") (pin "2") (pinfunction "ALERT/RDY_2") (pintype "bidirectional"))
    )
    (net (code "116") (name "unconnected-(IC5-ALERT{slash}RDY-Pad2)") (class "Default")
      (node (ref "IC5") (pin "2") (pinfunction "ALERT/RDY_2") (pintype "bidirectional"))
    )
    (net (code "117") (name "unconnected-(IC6-ALERT{slash}RDY-Pad2)") (class "Default")
      (node (ref "IC6") (pin "2") (pinfunction "ALERT/RDY_2") (pintype "bidirectional"))
    )
    (net (code "118") (name "unconnected-(IC7-ALERT{slash}RDY-Pad2)") (class "Default")
      (node (ref "IC7") (pin "2") (pinfunction "ALERT/RDY_2") (pintype "bidirectional"))
    )
    (net (code "119") (name "unconnected-(J1-A0_SHARED-PadA0)") (class "Default")
      (node (ref "J1") (pin "A0") (pinfunction "A0_SHARED_A0") (pintype "bidirectional"))
    )
    (net (code "120") (name "unconnected-(J1-A1_SHARED-PadA1)") (class "Default")
      (node (ref "J1") (pin "A1") (pinfunction "A1_SHARED_A1") (pintype "bidirectional"))
    )
    (net (code "121") (name "unconnected-(J1-A2_SHARED-PadA2)") (class "Default")
      (node (ref "J1") (pin "A2") (pinfunction "A2_SHARED_A2") (pintype "bidirectional"))
    )
    (net (code "122") (name "unconnected-(J1-D9_SHARED-PadD9)") (class "Default")
      (node (ref "J1") (pin "D9") (pinfunction "D9_SHARED_D9") (pintype "bidirectional"))
    )
    (net (code "123") (name "unconnected-(J1-D10_SHARED-PadD10)") (class "Default")
      (node (ref "J1") (pin "D10") (pinfunction "D10_SHARED_D10") (pintype "bidirectional"))
    )
    (net (code "124") (name "unconnected-(J1-D11_SHARED-PadD11)") (class "Default")
      (node (ref "J1") (pin "D11") (pinfunction "D11_SHARED_D11") (pintype "bidirectional"))
    )
    (net (code "125") (name "unconnected-(J1-PadA3)") (class "Default")
      (node (ref "J1") (pin "A3") (pinfunction "A3_A3") (pintype "bidirectional"))
    )
    (net (code "126") (name "unconnected-(J1-PadA4)") (class "Default")
      (node (ref "J1") (pin "A4") (pinfunction "A4_A4") (pintype "bidirectional"))
    )
    (net (code "127") (name "unconnected-(J1-PadA5)") (class "Default")
      (node (ref "J1") (pin "A5") (pinfunction "A5_A5") (pintype "bidirectional"))
    )
    (net (code "128") (name "unconnected-(J1-PadD0{slash}RX)") (class "Default")
      (node (ref "J1") (pin "D0/RX") (pinfunction "D0/RX_D0/RX") (pintype "bidirectional"))
    )
    (net (code "129") (name "unconnected-(J1-PadD1{slash}TX)") (class "Default")
      (node (ref "J1") (pin "D1/TX") (pinfunction "D1/TX_D1/TX") (pintype "bidirectional"))
    )
    (net (code "130") (name "unconnected-(J1-PadD4)") (class "Default")
      (node (ref "J1") (pin "D4") (pinfunction "D4_D4") (pintype "bidirectional"))
    )
    (net (code "131") (name "unconnected-(J1-PadD5)") (class "Default")
      (node (ref "J1") (pin "D5") (pinfunction "D5_D5") (pintype "bidirectional"))
    )
    (net (code "132") (name "unconnected-(J1-PadD6)") (class "Default")
      (node (ref "J1") (pin "D6") (pinfunction "D6_D6") (pintype "bidirectional"))
    )
    (net (code "133") (name "unconnected-(J1-PadD8)") (class "Default")
      (node (ref "J1") (pin "D8") (pinfunction "D8_D8") (pintype "bidirectional"))
    )
    (net (code "134") (name "unconnected-(J1-PadD14{slash}MISO)") (class "Default")
      (node (ref "J1") (pin "D14/MISO") (pinfunction "D14/MISO_D14/MISO") (pintype "bidirectional"))
    )
    (net (code "135") (name "unconnected-(J1-PadD15{slash}SCK)") (class "Default")
      (node (ref "J1") (pin "D15/SCK") (pinfunction "D15/SCK_D15/SCK") (pintype "bidirectional"))
    )
    (net (code "136") (name "unconnected-(J1-PadD16{slash}MOSI)") (class "Default")
      (node (ref "J1") (pin "D16/MOSI") (pinfunction "D16/MOSI_D16/MOSI") (pintype "bidirectional"))
    )
    (net (code "137") (name "unconnected-(J1-PadRESET)") (class "Default")
      (node (ref "J1") (pin "RESET") (pinfunction "RESET_RESET") (pintype "input"))
    )
    (net (code "138") (name "unconnected-(Q1-D-Pad3)") (class "Default")
      (node (ref "Q1") (pin "3") (pinfunction "D_3") (pintype "passive"))
    )
    (net (code "139") (name "unconnected-(Q1-G-Pad1)") (class "Default")
      (node (ref "Q1") (pin "1") (pinfunction "G_1") (pintype "passive"))
    )
    (net (code "140") (name "unconnected-(Q1-S-Pad2)") (class "Default")
      (node (ref "Q1") (pin "2") (pinfunction "S_2") (pintype "passive"))
    )
    (net (code "141") (name "unconnected-(Q2-D-Pad3)") (class "Default")
      (node (ref "Q2") (pin "3") (pinfunction "D_3") (pintype "passive"))
    )
    (net (code "142") (name "unconnected-(Q2-G-Pad1)") (class "Default")
      (node (ref "Q2") (pin "1") (pinfunction "G_1") (pintype "passive"))
    )
    (net (code "143") (name "unconnected-(Q2-S-Pad2)") (class "Default")
      (node (ref "Q2") (pin "2") (pinfunction "S_2") (pintype "passive"))
    )
    (net (code "144") (name "unconnected-(R10-Pad1)") (class "Default")
      (node (ref "R10") (pin "1") (pinfunction "1_1") (pintype "passive"))
    )
    (net (code "145") (name "unconnected-(R10-Pad2)") (class "Default")
      (node (ref "R10") (pin "2") (pinfunction "2_2") (pintype "passive"))
    )
    (net (code "146") (name "unconnected-(R11-Pad1)") (class "Default")
      (node (ref "R11") (pin "1") (pinfunction "1_1") (pintype "passive"))
    )
    (net (code "147") (name "unconnected-(R11-Pad2)") (class "Default")
      (node (ref "R11") (pin "2") (pinfunction "2_2") (pintype "passive"))
    )
    (net (code "148") (name "unconnected-(R12-Pad1)") (class "Default")
      (node (ref "R12") (pin "1") (pinfunction "1_1") (pintype "passive"))
    )
    (net (code "149") (name "unconnected-(R12-Pad2)") (class "Default")
      (node (ref "R12") (pin "2") (pinfunction "2_2") (pintype "passive"))
    )
    (net (code "150") (name "unconnected-(R13-Pad1)") (class "Default")
      (node (ref "R13") (pin "1") (pinfunction "1_1") (pintype "passive"))
    )
    (net (code "151") (name "unconnected-(R13-Pad2)") (class "Default")
      (node (ref "R13") (pin "2") (pinfunction "2_2") (pintype "passive"))
    )
    (net (code "152") (name "unconnected-(R14-Pad1)") (class "Default")
      (node (ref "R14") (pin "1") (pinfunction "1_1") (pintype "passive"))
    )
    (net (code "153") (name "unconnected-(R14-Pad2)") (class "Default")
      (node (ref "R14") (pin "2") (pinfunction "2_2") (pintype "passive"))
    )
  )
)
